# AC-DC24_Overall.net
KiCad netlist of a schematic drawn in Altium Designer
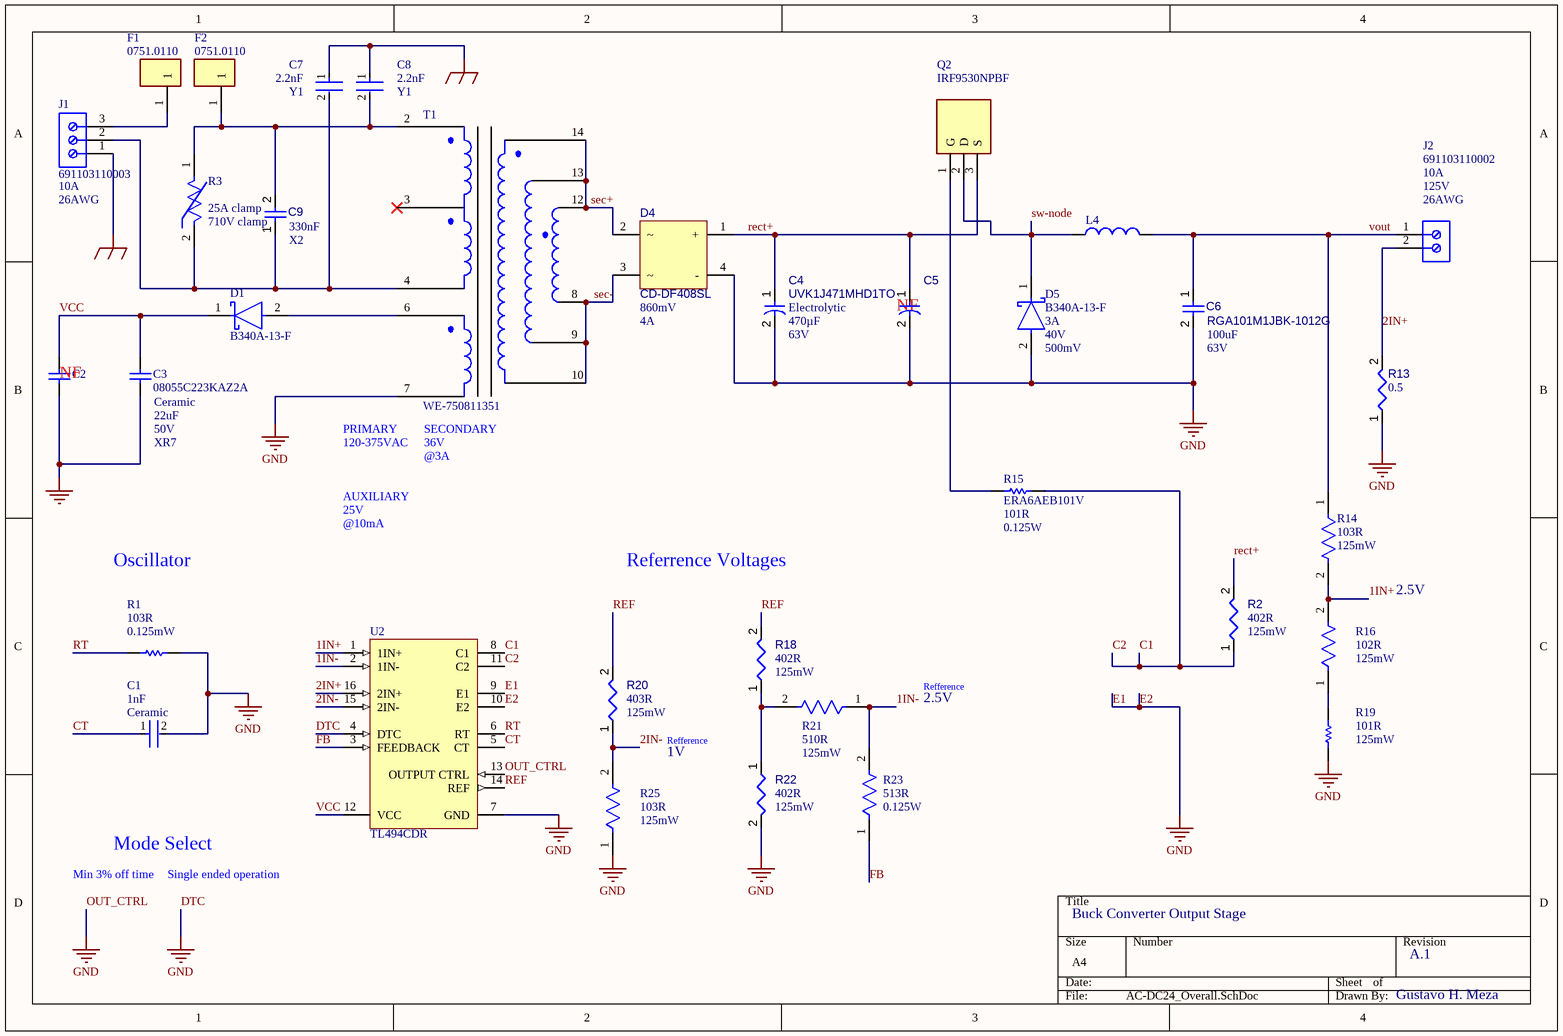
[diagram p0: AC-DC24_Overall.SchDoc]

(export (version "E")
  (design (tool "Eeschema 10.0.6"))
  (components
    (comp (ref "C1")
      (value "08051A102JAT2A")
      (footprint "FP-0805-L_2_01_0_2-W_1_25-MFG")
      (description "General Purpose Ceramic Capacitor, 0805, 1nF, 5%, C0G, 30ppm/°C, 100V")
      (fields
        (field (name "VOLTAGE") "100V")
        (field (name "CAPACITANCE") "1nF")
        (field (name "TOLERANCE") "5%")
        (field (name "DIELECTRIC MATERIAL") "Ceramic")
      )
      (libsource (lib "Altium Content Vault") (part "02cd4be3c70576c341d710602a673aa"))
    )
    (comp (ref "C2")
      (value "08055C223KAZ2A")
      (footprint "CAPC2013X94X50ML20T25")
      (fields (field (name "MANUFACTURER") "AVX Interconnect / Elco"))
      (libsource (lib "Altium Content Vault") (part "CAP"))
    )
    (comp (ref "C3")
      (value "08055C223KAZ2A")
      (footprint "CAPC2013X94X50ML20T25")
      (fields
        (field (name "MANUFACTURER") "AVX Interconnect / Elco")
        (field (name "MATERIAL") "Ceramic")
        (field (name "DIELECTRIC") "XR7")
        (field (name "VOLTAGE RATING") "50V")
        (field (name "CAPACITANCE") "22uF")
      )
      (libsource (lib "Altium Content Vault") (part "CAP"))
    )
    (comp (ref "C4")
      (value "UVK1J471MHD1TO")
      (footprint "UVK1J471MHD1TO-Footprint-1")
      (description "Cap Alum 470UF 20% 63V Radial")
      (fields
        (field (name "CAPACITOR TYPE") "Electrolytic")
        (field (name "ALTIUM_VALUE") "470µF")
        (field (name "VOLTAGE RATING") "63V")
      )
      (libsource (lib "") (part "CAP-NP-2_1"))
    )
    (comp (ref "C5")
      (value "UVK1J471MHD1TO")
      (footprint "UVK1J471MHD1TO-Footprint-1")
      (description "Cap Alum 470UF 20% 63V Radial")
      (libsource (lib "") (part "CAP-NP-2_1"))
    )
    (comp (ref "C6")
      (value "RGA101M1JBK-1012G")
      (footprint "RGA101M1JBK-1012G-Footprint-1")
      (description "Aluminum Electrolytic Capacitors - Leaded 63V 100uF 105C 10x12.5 mm")
      (fields (field (name "VOLTAGE RATING") "63V") (field (name "CAPACITANCE") "100uF"))
      (libsource (lib "Cetys University") (part "CAP-NP-2"))
    )
    (comp (ref "C7")
      (value "VY1222M47Y5UQ6TV0")
      (footprint "FP-VY1470-MFG")
      (description "CAP CER 2200PF 760VAC Y5U RADIAL")
      (fields
        (field (name "CAPACITANCE") "2.2nF")
        (field (name "VOLTAGE") "500V")
        (field (name "TOLERANCE") "20%")
        (field (name "SAFETY RATING") "Y1")
      )
      (libsource (lib "Altium Content Vault") (part "11868f565c42a9108669ba33697ecf6"))
    )
    (comp (ref "C8")
      (value "VY1222M47Y5UQ6TV0")
      (footprint "FP-VY1470-MFG")
      (description "CAP CER 2200PF 760VAC Y5U RADIAL")
      (fields
        (field (name "CAPACITANCE") "2.2nF")
        (field (name "VOLTAGE") "500V")
        (field (name "TOLERANCE") "20%")
        (field (name "SAFETY RATING") "Y1")
      )
      (libsource (lib "Altium Content Vault") (part "11868f565c42a9108669ba33697ecf6"))
    )
    (comp (ref "C9")
      (value "330nF")
      (footprint "B32922C3334M000-Footprint-1")
      (description "Film Capacitor, Polypropylene, 630V, 20% +Tol, 20% -Tol, 0.33uF, Through Hole Mount")
      (fields (field (name "SAFETY RATING") "X2") (field (name "Comment") "B32922C3334M000"))
      (libsource (lib "Cetys University") (part "CAP-NP-2"))
    )
    (comp (ref "D1")
      (value "B340A-13-F")
      (footprint "FP-SMA-MFG")
      (description "DIODE SCHOTTKY 40V 3A SMA")
      (fields (field (name "VOLTAGE") "40V"))
      (libsource (lib "Altium Content Vault") (part "1d6ec82d83fb6aee721767c19dac4b9"))
    )
    (comp (ref "D4")
      (value "CD-DF408SL")
      (footprint "CD-DF408SL-Footprint-1")
      (description "Bridge Rectifier Diode, 1 Phase, 4A, 800V V(RRM), Silicon")
      (fields (field (name "FORWARD VOLTAGE") "860mV") (field (name "FORWARD CURRENT") "4A"))
      (libsource (lib "Cetys University") (part "DIODE-2"))
    )
    (comp (ref "D5")
      (value "B340A-13-F")
      (footprint "FP-SMA-MFG")
      (description "DIODE SCHOTTKY 40V 3A SMA")
      (fields
        (field (name "OUTPUT CURRENT") "3A")
        (field (name "VOLTAGE") "40V")
        (field (name "FORWARD VOLTAGE") "500mV")
      )
      (libsource (lib "Altium Content Vault") (part "1d6ec82d83fb6aee721767c19dac4b9"))
    )
    (comp (ref "F1")
      (value "0751.0110")
      (footprint "FP-0751_0110-MFG")
      (description "FUSE CLIP CARTRIDGE 10A PCB")
      (fields
        (field (name "OCTOPART") "https://octopart.com/0751.0110-schurter-19402")
        (field (name "MANUFACTURER") "Schurter")
      )
      (libsource (lib "Altium Content Vault") (part "6594cd1380bf084bed0a40489f8b218"))
    )
    (comp (ref "F2")
      (value "0751.0110")
      (footprint "FP-0751_0110-MFG")
      (description "FUSE CLIP CARTRIDGE 10A PCB")
      (fields
        (field (name "OCTOPART") "https://octopart.com/0751.0110-schurter-19402")
        (field (name "MANUFACTURER") "Schurter")
      )
      (libsource (lib "Altium Content Vault") (part "6594cd1380bf084bed0a40489f8b218"))
    )
    (comp (ref "J1")
      (value "691103110003")
      (footprint "691103110003")
      (fields (field (name "CURRENT RATING") "10A") (field (name "WIRE/CABLE GAUGE") "26AWG"))
      (libsource (lib "Altium Content Vault") (part "TBL - 1R - 03P - Screw"))
    )
    (comp (ref "J2")
      (value "691103110002")
      (footprint "691103110002")
      (fields
        (field (name "CURRENT RATING") "10A")
        (field (name "VOLTAGE") "125V")
        (field (name "WIRE/CABLE GAUGE") "26AWG")
      )
      (libsource (lib "Altium Content Vault") (part "TBL - 1R - 02P - Screw"))
    )
    (comp (ref "L4")
      (value "FIT80-1")
      (footprint "FIT80-1-Footprint-1")
      (description "General Purpose Inductor, 128uH, 1 Element, 9863")
      (libsource (lib "Cetys University") (part "IND-2"))
    )
    (comp (ref "Q2")
      (value "IRF9530NPBF")
      (footprint "TO254P469X1042X1967-3P")
      (description "MOSFET MOSFT PCh -100V -14A 200mOhm 38.7nC")
      (fields (field (name "MOUSER PART NUMBER") "942-IRF9530NPBF"))
      (libsource (lib "Cetys University") (part "IRF9530NPBF"))
    )
    (comp (ref "R1")
      (value "RC0805JR-0710KL")
      (footprint "RESC2013X60X35ML10T20")
      (description "Chip Resistor, 10 KOhm, +/- 5%, 0.125 W, -55 to 155 degC, 0805 (2012 Metric), RoHS, Tape and Reel")
      (fields
        (field (name "MANUFACTURER") "Yageo")
        (field (name "RESISTANCE") "103R")
        (field (name "POWER") "0.125mW")
      )
      (libsource (lib "Altium Content Vault") (part "RES-2"))
    )
    (comp (ref "R2")
      (value "402R")
      (footprint "RESC3416X05N")
      (description "RES SMD 4K OHM 1% 1/8W 0805")
      (fields
        (field (name "POWER") "125mW")
        (field (name "TOLERANCE") "1%")
        (field (name "Comment") "CRCW08054K00FKTA")
      )
      (libsource (lib "Cetys University") (part "RES-2"))
    )
    (comp (ref "R3")
      (value "B72210S2271K101")
      (footprint "FP-B72210S2271K101-MFG")
      (description "VARISTOR 430V 3.5KA DISC 10MM")
      (fields
        (field (name "CLAMPING CURRENT") "25A clamp")
        (field (name "OCTOPART") "https://octopart.com/b72210s2271k101-epcos-42227876")
        (field (name "MANUFACTURER") "EPCOS")
        (field (name "CLAMPING VOLTAGE") "710V clamp")
      )
      (libsource (lib "Altium Content Vault") (part "78a88060d5b7b043d6e48adc4284376"))
    )
    (comp (ref "R13")
      (value "0.5")
      (footprint "RS02CR5000FB12-Footprint-1")
      (description "Fixed Resistor, Wire Wound, 2.5W, 0.5ohm, 1% +/-Tol, 90ppm/Cel, Through Hole Mount")
      (fields (field (name "TOLERANCE") "1%") (field (name "POWER") "2.5W"))
      (libsource (lib "Cetys University") (part "RES-2"))
    )
    (comp (ref "R14")
      (value "CRCW080510K0FKEA")
      (footprint "FP-CRCW0805-e3-IPC_A")
      (description "RES Thick Film, 10kΩ, 1%, 0.125W, 100ppm/°C, 0805")
      (fields
        (field (name "RESISTANCE") "103R")
        (field (name "TOLERANCE") "1%")
        (field (name "POWER RATING") "125mW")
      )
      (libsource (lib "Altium Content Vault") (part "1029c3af85768c4190bb7ad29bc67b5"))
    )
    (comp (ref "R15")
      (value "ERA6AEB101V")
      (footprint "RESC2013X60X40ML20T25")
      (fields
        (field (name "MANUFACTURER") "Panasonic")
        (field (name "RESISTANCE") "101R")
        (field (name "POWER RATING") "0.125W")
      )
      (libsource (lib "Altium Content Vault") (part "RES"))
    )
    (comp (ref "R16")
      (value "CRCW08051K00JNEA")
      (footprint "FP-CRCW0805-e3-IPC_B")
      (description "RES Thick Film, 1kΩ, 5%, 0.125W, 200ppm/°C, 0805")
      (fields
        (field (name "POWER RATING") "125mW")
        (field (name "RESISTANCE") "102R")
        (field (name "TOLERANCE") "5%")
      )
      (libsource (lib "Altium Content Vault") (part "1029c3af85768c4190bb7ad29bc67b5"))
    )
    (comp (ref "R18")
      (value "402R")
      (footprint "RESC3416X05N")
      (description "RES SMD 4K OHM 1% 1/8W 0805")
      (fields
        (field (name "POWER") "125mW")
        (field (name "TOLERANCE") "1%")
        (field (name "Comment") "CRCW08054K00FKTA")
      )
      (libsource (lib "Cetys University") (part "RES-2"))
    )
    (comp (ref "R19")
      (value "ERA6AEB101V")
      (footprint "RESC2013X60X40ML20T25")
      (fields
        (field (name "MANUFACTURER") "Panasonic")
        (field (name "RESISTANCEMETER 1") "101R")
        (field (name "POWER") "125mW")
      )
      (libsource (lib "Altium Content Vault") (part "RES"))
    )
    (comp (ref "R20")
      (value "403R")
      (footprint "RESC3416X05N")
      (description "RES SMD 4K OHM 1% 1/8W 0805")
      (fields
        (field (name "POWER") "125mW")
        (field (name "TOLERANCE") "1%")
        (field (name "Comment") "CRCW08054K00FKTA")
      )
      (libsource (lib "Cetys University") (part "RES-2"))
    )
    (comp (ref "R21")
      (value "CR0805JW511E")
      (footprint "FP-CR0805-IPC_B")
      (description "Thick Film Chip Resistors 0805 510Ω 0.125W 5% 200ppm/°C")
      (fields
        (field (name "RESISTANCE") "510R")
        (field (name "POWER RATING") "125mW")
        (field (name "TOLERANCE") "5%")
      )
      (libsource (lib "Altium Content Vault") (part "1029c3af85768c4190bb7ad29bc67b5"))
    )
    (comp (ref "R22")
      (value "402R")
      (footprint "RESC3416X05N")
      (description "RES SMD 4K OHM 1% 1/8W 0805")
      (fields
        (field (name "POWER") "125mW")
        (field (name "TOLERANCE") "1%")
        (field (name "Comment") "CRCW08054K00FKTA")
      )
      (libsource (lib "Cetys University") (part "RES-2"))
    )
    (comp (ref "R23")
      (value "513R")
      (footprint "FP-RT0805-MFG")
      (description "RES SMD 51K OHM 0.1% 1/8W 0805")
      (fields
        (field (name "MANUFACTURER") "Yageo")
        (field (name "TOLERANCE") "0.0025")
        (field (name "POWER RATING") "0.125W")
      )
      (libsource (lib "Altium Content Vault") (part "1029c3af85768c4190bb7ad29bc67b5"))
    )
    (comp (ref "R25")
      (value "ERA6AEB102V")
      (footprint "FP-ERA6A-IPC_C")
      (description "RES 1K OHM 0.1% 1/8W 0805")
      (fields
        (field (name "RESISTANCE") "103R")
        (field (name "MAX POWER DISSIPATION") "125mW")
        (field (name "TOLERANCE") "0.1%")
      )
      (libsource (lib "Altium Content Vault") (part "1029c3af85768c4190bb7ad29bc67b5"))
    )
    (comp (ref "T1")
      (value "WE-750811351")
      (footprint "WE-750811248-Footprint-1")
      (description "Power Transformers MID-L3798/99 Offline Isol 3.6uH +-10%")
      (fields (field (name "POWER") "48W"))
      (libsource (lib "Cetys University") (part "TFORM-4"))
    )
    (comp (ref "U2")
      (value "TL494CDR")
      (footprint "D0016A_N")
      (fields (field (name "MANUFACTURER") "Texas Instruments"))
      (libsource (lib "Altium Content Vault") (part "TI-494D16"))
    )
  )
  (nets
    (net (code "1") (name "/1IN+") (class "Default")
      (node (ref "R14") (pin "2") (pinfunction "2_2") (pintype "passive"))
      (node (ref "R16") (pin "2") (pinfunction "2_2") (pintype "passive"))
      (node (ref "U2") (pin "1") (pinfunction "1IN+_1") (pintype "input"))
    )
    (net (code "2") (name "/1IN-") (class "Default")
      (node (ref "R21") (pin "1") (pinfunction "1_1") (pintype "passive"))
      (node (ref "R23") (pin "2") (pinfunction "2_2") (pintype "passive"))
      (node (ref "U2") (pin "2") (pinfunction "1IN-_2") (pintype "input"))
    )
    (net (code "3") (name "/2IN+") (class "Default")
      (node (ref "J2") (pin "2") (pinfunction "2_2") (pintype "passive"))
      (node (ref "R13") (pin "2") (pinfunction "2_2") (pintype "passive"))
      (node (ref "U2") (pin "16") (pinfunction "2IN+_16") (pintype "input"))
    )
    (net (code "4") (name "/2IN-") (class "Default")
      (node (ref "R20") (pin "1") (pinfunction "1_1") (pintype "passive"))
      (node (ref "R25") (pin "2") (pinfunction "2_2") (pintype "passive"))
      (node (ref "U2") (pin "15") (pinfunction "2IN-_15") (pintype "input"))
    )
    (net (code "5") (name "/C1") (class "Default")
      (node (ref "R15") (pin "1") (pinfunction "1_1") (pintype "passive"))
      (node (ref "R2") (pin "1") (pinfunction "1_1") (pintype "passive"))
      (node (ref "U2") (pin "11") (pinfunction "C2_11") (pintype "passive"))
      (node (ref "U2") (pin "8") (pinfunction "C1_8") (pintype "passive"))
    )
    (net (code "6") (name "/CT") (class "Default")
      (node (ref "C1") (pin "1") (pinfunction "1_1") (pintype "passive"))
      (node (ref "U2") (pin "5") (pinfunction "CT_5") (pintype "passive"))
    )
    (net (code "7") (name "/FB") (class "Default")
      (node (ref "R23") (pin "1") (pinfunction "1_1") (pintype "passive"))
      (node (ref "U2") (pin "3") (pinfunction "FEEDBACK_3") (pintype "input"))
    )
    (net (code "8") (name "/REF") (class "Default")
      (node (ref "R18") (pin "2") (pinfunction "2_2") (pintype "passive"))
      (node (ref "R20") (pin "2") (pinfunction "2_2") (pintype "passive"))
      (node (ref "U2") (pin "14") (pinfunction "REF_14") (pintype "output"))
    )
    (net (code "9") (name "/RT") (class "Default")
      (node (ref "R1") (pin "1") (pinfunction "1_1") (pintype "passive"))
      (node (ref "U2") (pin "6") (pinfunction "RT_6") (pintype "passive"))
    )
    (net (code "10") (name "/VCC") (class "Default")
      (node (ref "C2") (pin "2") (pinfunction "2_2") (pintype "passive"))
      (node (ref "C3") (pin "2") (pinfunction "2_2") (pintype "passive"))
      (node (ref "D1") (pin "1") (pinfunction "C_1") (pintype "passive"))
      (node (ref "U2") (pin "12") (pinfunction "VCC_12") (pintype "power_in"))
    )
    (net (code "11") (name "/rect+") (class "Default")
      (node (ref "C4") (pin "1") (pinfunction "1_1") (pintype "passive"))
      (node (ref "C5") (pin "1") (pinfunction "1_1") (pintype "passive"))
      (node (ref "D4") (pin "1") (pinfunction "+_1") (pintype "passive"))
      (node (ref "Q2") (pin "3") (pinfunction "S_3") (pintype "passive"))
      (node (ref "R2") (pin "2") (pinfunction "2_2") (pintype "passive"))
    )
    (net (code "12") (name "/sec+") (class "Default")
      (node (ref "D4") (pin "2") (pinfunction "~_2") (pintype "passive"))
      (node (ref "T1") (pin "12") (pinfunction "12_12") (pintype "passive"))
      (node (ref "T1") (pin "13") (pinfunction "13_13") (pintype "passive"))
      (node (ref "T1") (pin "14") (pinfunction "14_14") (pintype "passive"))
    )
    (net (code "13") (name "/sec-") (class "Default")
      (node (ref "D4") (pin "3") (pinfunction "~_3") (pintype "passive"))
      (node (ref "T1") (pin "10") (pinfunction "10_10") (pintype "passive"))
      (node (ref "T1") (pin "8") (pinfunction "8_8") (pintype "passive"))
      (node (ref "T1") (pin "9") (pinfunction "9_9") (pintype "passive"))
    )
    (net (code "14") (name "/sw-node") (class "Default")
      (node (ref "D5") (pin "1") (pinfunction "C_1") (pintype "passive"))
      (node (ref "L4") (pin "1") (pinfunction "1_1") (pintype "passive"))
      (node (ref "Q2") (pin "2") (pinfunction "D_2") (pintype "passive"))
    )
    (net (code "15") (name "/vout") (class "Default")
      (node (ref "C6") (pin "1") (pinfunction "1_1") (pintype "passive"))
      (node (ref "J2") (pin "1") (pinfunction "1_1") (pintype "passive"))
      (node (ref "L4") (pin "2") (pinfunction "2_2") (pintype "passive"))
      (node (ref "R14") (pin "1") (pinfunction "1_1") (pintype "passive"))
    )
    (net (code "16") (name "GND") (class "Default")
      (node (ref "C1") (pin "2") (pinfunction "2_2") (pintype "passive"))
      (node (ref "C2") (pin "1") (pinfunction "1_1") (pintype "passive"))
      (node (ref "C3") (pin "1") (pinfunction "1_1") (pintype "passive"))
      (node (ref "C4") (pin "2") (pinfunction "2_2") (pintype "passive"))
      (node (ref "C5") (pin "2") (pinfunction "2_2") (pintype "passive"))
      (node (ref "C6") (pin "2") (pinfunction "2_2") (pintype "passive"))
      (node (ref "C7") (pin "1") (pinfunction "1_1") (pintype "passive"))
      (node (ref "C8") (pin "1") (pinfunction "1_1") (pintype "passive"))
      (node (ref "D4") (pin "4") (pinfunction "-_4") (pintype "passive"))
      (node (ref "D5") (pin "2") (pinfunction "A_2") (pintype "passive"))
      (node (ref "J1") (pin "1") (pinfunction "1_1") (pintype "passive"))
      (node (ref "R1") (pin "2") (pinfunction "2_2") (pintype "passive"))
      (node (ref "R13") (pin "1") (pinfunction "1_1") (pintype "passive"))
      (node (ref "R19") (pin "1") (pinfunction "1_1") (pintype "passive"))
      (node (ref "R22") (pin "2") (pinfunction "2_2") (pintype "passive"))
      (node (ref "R25") (pin "1") (pinfunction "1_1") (pintype "passive"))
      (node (ref "T1") (pin "7") (pinfunction "7_7") (pintype "passive"))
      (node (ref "U2") (pin "10") (pinfunction "E2_10") (pintype "passive"))
      (node (ref "U2") (pin "13") (pinfunction "OUTPUT_CTRL_13") (pintype "input"))
      (node (ref "U2") (pin "4") (pinfunction "DTC_4") (pintype "input"))
      (node (ref "U2") (pin "7") (pinfunction "GND_7") (pintype "power_in"))
      (node (ref "U2") (pin "9") (pinfunction "E1_9") (pintype "passive"))
    )
    (net (code "17") (name "Net-(C7-Pad2)") (class "Default")
      (node (ref "C7") (pin "2") (pinfunction "2_2") (pintype "passive"))
      (node (ref "C9") (pin "1") (pinfunction "1_1") (pintype "passive"))
      (node (ref "J1") (pin "2") (pinfunction "2_2") (pintype "passive"))
      (node (ref "R3") (pin "2") (pinfunction "2_2") (pintype "passive"))
      (node (ref "T1") (pin "4") (pinfunction "4_4") (pintype "passive"))
    )
    (net (code "18") (name "Net-(C8-Pad2)") (class "Default")
      (node (ref "C8") (pin "2") (pinfunction "2_2") (pintype "passive"))
      (node (ref "C9") (pin "2") (pinfunction "2_2") (pintype "passive"))
      (node (ref "F2") (pin "1") (pinfunction "1_1") (pintype "passive"))
      (node (ref "R3") (pin "1") (pinfunction "1_1") (pintype "passive"))
      (node (ref "T1") (pin "2") (pinfunction "2_2") (pintype "passive"))
    )
    (net (code "19") (name "Net-(D1-A)") (class "Default")
      (node (ref "D1") (pin "2") (pinfunction "A_2") (pintype "passive"))
      (node (ref "T1") (pin "6") (pinfunction "6_6") (pintype "passive"))
    )
    (net (code "20") (name "Net-(F1-Pad1)") (class "Default")
      (node (ref "F1") (pin "1") (pinfunction "1_1") (pintype "passive"))
      (node (ref "J1") (pin "3") (pinfunction "3_3") (pintype "passive"))
    )
    (net (code "21") (name "Net-(Q2-G)") (class "Default")
      (node (ref "Q2") (pin "1") (pinfunction "G_1") (pintype "passive"))
      (node (ref "R15") (pin "2") (pinfunction "2_2") (pintype "passive"))
    )
    (net (code "22") (name "Net-(R16-Pad1)") (class "Default")
      (node (ref "R16") (pin "1") (pinfunction "1_1") (pintype "passive"))
      (node (ref "R19") (pin "2") (pinfunction "2_2") (pintype "passive"))
    )
    (net (code "23") (name "Net-(R18-Pad1)") (class "Default")
      (node (ref "R18") (pin "1") (pinfunction "1_1") (pintype "passive"))
      (node (ref "R21") (pin "2") (pinfunction "2_2") (pintype "passive"))
      (node (ref "R22") (pin "1") (pinfunction "1_1") (pintype "passive"))
    )
    (net (code "24") (name "unconnected-(T1-Pad1)") (class "Default")
      (node (ref "T1") (pin "1") (pinfunction "1_1") (pintype "passive"))
    )
    (net (code "25") (name "unconnected-(T1-Pad1)_1") (class "Default")
      (node (ref "T1") (pin "1") (pinfunction "1_1") (pintype "passive"))
    )
    (net (code "26") (name "unconnected-(T1-Pad1)_2") (class "Default")
      (node (ref "T1") (pin "1") (pinfunction "1_1") (pintype "passive"))
    )
    (net (code "27") (name "unconnected-(T1-Pad2)") (class "Default")
      (node (ref "T1") (pin "2") (pinfunction "2_2") (pintype "passive"))
    )
    (net (code "28") (name "unconnected-(T1-Pad2)_1") (class "Default")
      (node (ref "T1") (pin "2") (pinfunction "2_2") (pintype "passive"))
    )
    (net (code "29") (name "unconnected-(T1-Pad2)_2") (class "Default")
      (node (ref "T1") (pin "2") (pinfunction "2_2") (pintype "passive"))
    )
    (net (code "30") (name "unconnected-(T1-Pad2)_3") (class "Default")
      (node (ref "T1") (pin "2") (pinfunction "2_2") (pintype "passive"))
    )
    (net (code "31") (name "unconnected-(T1-Pad3)") (class "Default")
      (node (ref "T1") (pin "3") (pinfunction "3_3") (pintype "passive+no_connect"))
    )
    (net (code "32") (name "unconnected-(T1-Pad3)") (class "Default")
      (node (ref "T1") (pin "3") (pinfunction "3_3") (pintype "passive"))
    )
    (net (code "33") (name "unconnected-(T1-Pad4)") (class "Default")
      (node (ref "T1") (pin "4") (pinfunction "4_4") (pintype "passive"))
    )
  )
)
